# display_zm1000.net
KiCad netlist of a schematic drawn in EAGLE
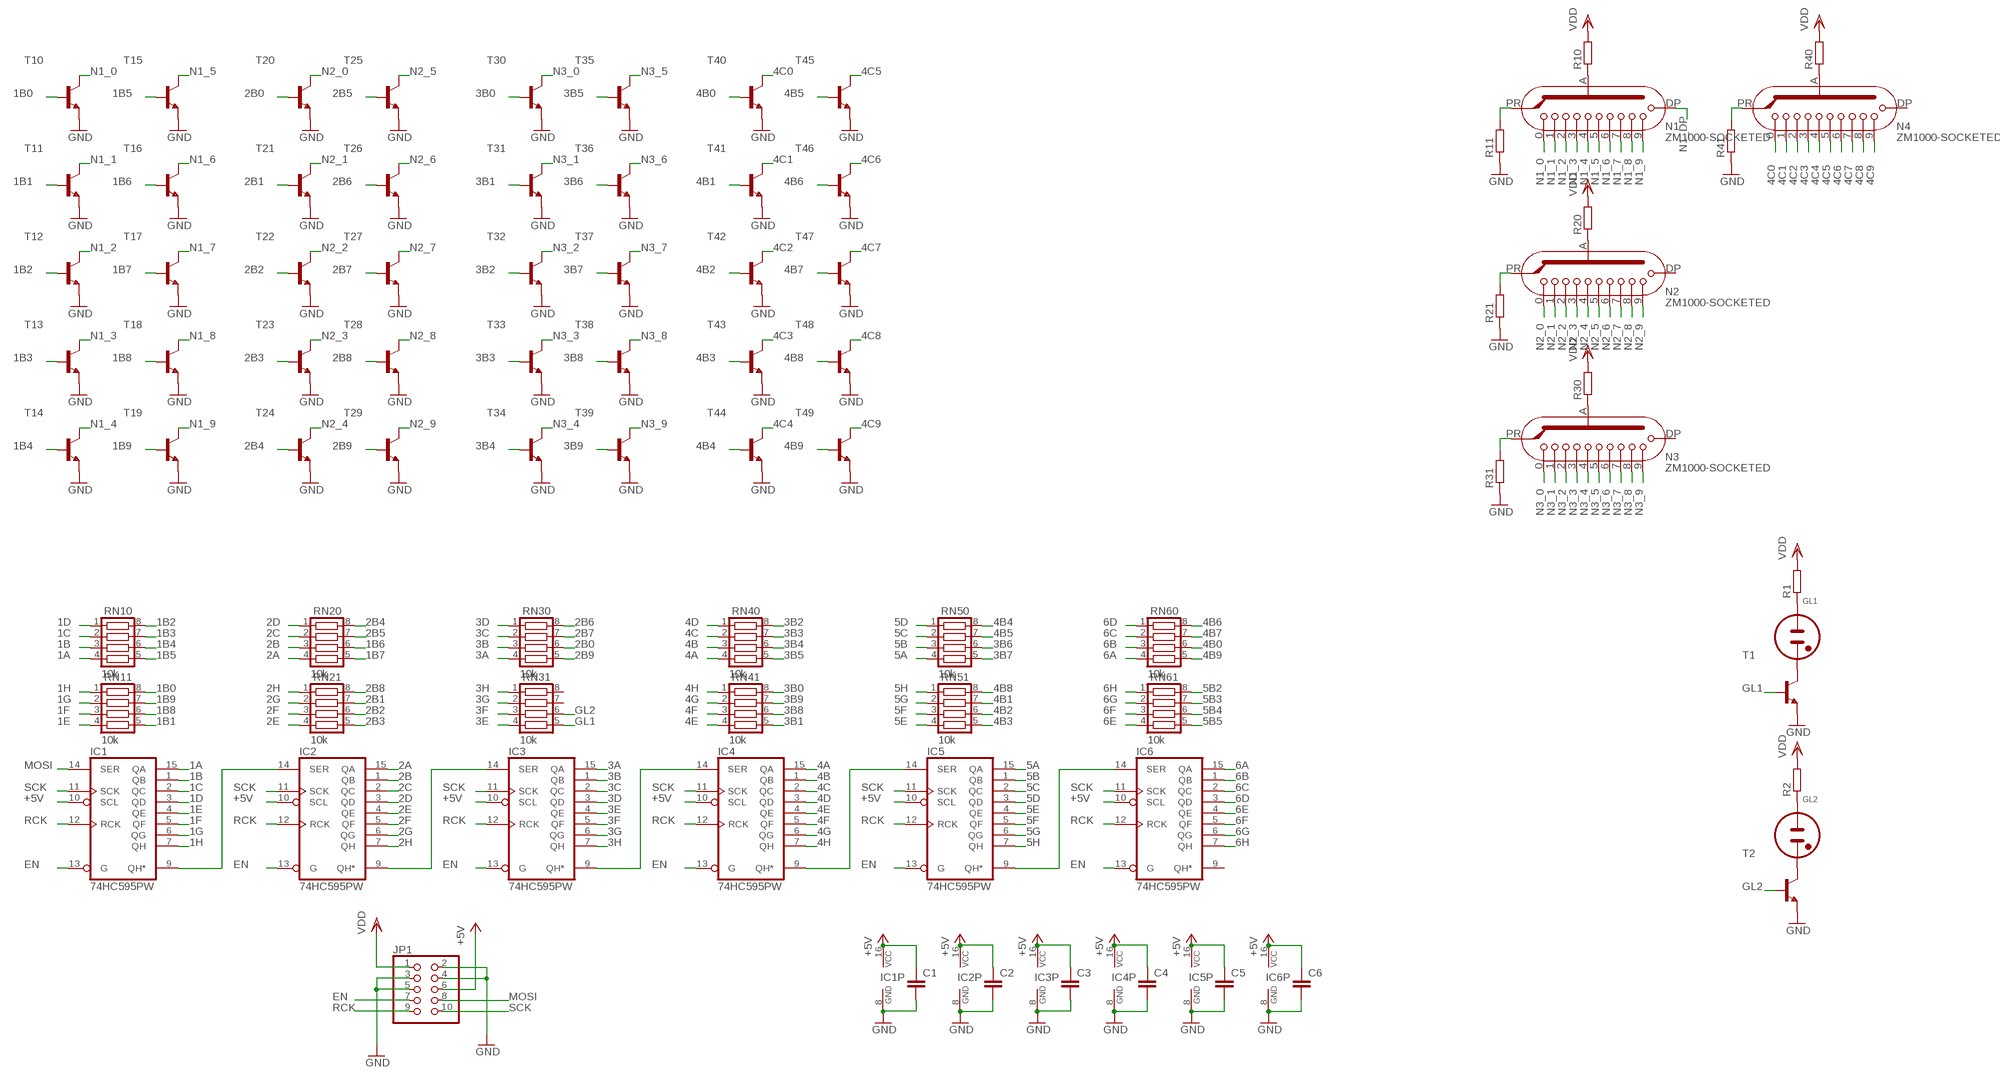
[diagram p0: schematic, sheet 1]

(export (version "E")
  (design (tool "Eeschema 10.0.6"))
  (components
    (comp (ref "C1")
      (value "C-EUC0603")
      (footprint "eagle-import:C0603")
      (libsource (lib "eagle-import") (part "C-EUC0603"))
    )
    (comp (ref "C2")
      (value "C-EUC0603")
      (footprint "eagle-import:C0603")
      (libsource (lib "eagle-import") (part "C-EUC0603"))
    )
    (comp (ref "C3")
      (value "C-EUC0603")
      (footprint "eagle-import:C0603")
      (libsource (lib "eagle-import") (part "C-EUC0603"))
    )
    (comp (ref "C4")
      (value "C-EUC0603")
      (footprint "eagle-import:C0603")
      (libsource (lib "eagle-import") (part "C-EUC0603"))
    )
    (comp (ref "C5")
      (value "C-EUC0603")
      (footprint "eagle-import:C0603")
      (libsource (lib "eagle-import") (part "C-EUC0603"))
    )
    (comp (ref "C6")
      (value "C-EUC0603")
      (footprint "eagle-import:C0603")
      (libsource (lib "eagle-import") (part "C-EUC0603"))
    )
    (comp (ref "GL1")
      (value "NE2-NEON-BULB-DRILL")
      (footprint "eagle-import:NE2-NEON-BULB-DRILL")
      (libsource (lib "eagle-import") (part "NE2-NEON-BULB-DRILL"))
    )
    (comp (ref "GL2")
      (value "NE2-NEON-BULB-DRILL")
      (footprint "eagle-import:NE2-NEON-BULB-DRILL")
      (libsource (lib "eagle-import") (part "NE2-NEON-BULB-DRILL"))
    )
    (comp (ref "IC1")
      (value "74HC595PW")
      (footprint "eagle-import:TSSOP16")
      (libsource (lib "eagle-import") (part "74595PWHC"))
    )
    (comp (ref "IC2")
      (value "74HC595PW")
      (footprint "eagle-import:TSSOP16")
      (libsource (lib "eagle-import") (part "74595PWHC"))
    )
    (comp (ref "IC3")
      (value "74HC595PW")
      (footprint "eagle-import:TSSOP16")
      (libsource (lib "eagle-import") (part "74595PWHC"))
    )
    (comp (ref "IC4")
      (value "74HC595PW")
      (footprint "eagle-import:TSSOP16")
      (libsource (lib "eagle-import") (part "74595PWHC"))
    )
    (comp (ref "IC5")
      (value "74HC595PW")
      (footprint "eagle-import:TSSOP16")
      (libsource (lib "eagle-import") (part "74595PWHC"))
    )
    (comp (ref "IC6")
      (value "74HC595PW")
      (footprint "eagle-import:TSSOP16")
      (libsource (lib "eagle-import") (part "74595PWHC"))
    )
    (comp (ref "JP1")
      (value "PINHD-2X5_2.54-SMD")
      (footprint "eagle-import:2X05SMD")
      (libsource (lib "eagle-import") (part "PINHD-2X5_2.54-SMD"))
    )
    (comp (ref "N1")
      (value "ZM1000-SOCKETED")
      (footprint "eagle-import:ZM1000-SOCKETED")
      (libsource (lib "eagle-import") (part "ZM1000-SOCKETED"))
    )
    (comp (ref "N2")
      (value "ZM1000-SOCKETED")
      (footprint "eagle-import:ZM1000-SOCKETED")
      (libsource (lib "eagle-import") (part "ZM1000-SOCKETED"))
    )
    (comp (ref "N3")
      (value "ZM1000-SOCKETED")
      (footprint "eagle-import:ZM1000-SOCKETED")
      (libsource (lib "eagle-import") (part "ZM1000-SOCKETED"))
    )
    (comp (ref "N4")
      (value "ZM1000-SOCKETED")
      (footprint "eagle-import:ZM1000-SOCKETED")
      (libsource (lib "eagle-import") (part "ZM1000-SOCKETED"))
    )
    (comp (ref "R1")
      (value "R-EU_R0603")
      (footprint "eagle-import:R0603")
      (libsource (lib "eagle-import") (part "R-EU_R0603"))
    )
    (comp (ref "R2")
      (value "R-EU_R0603")
      (footprint "eagle-import:R0603")
      (libsource (lib "eagle-import") (part "R-EU_R0603"))
    )
    (comp (ref "R10")
      (value "R-EU_R0603")
      (footprint "eagle-import:R0603")
      (libsource (lib "eagle-import") (part "R-EU_R0603"))
    )
    (comp (ref "R11")
      (value "R-EU_R0603")
      (footprint "eagle-import:R0603")
      (libsource (lib "eagle-import") (part "R-EU_R0603"))
    )
    (comp (ref "R20")
      (value "R-EU_R0603")
      (footprint "eagle-import:R0603")
      (libsource (lib "eagle-import") (part "R-EU_R0603"))
    )
    (comp (ref "R21")
      (value "R-EU_R0603")
      (footprint "eagle-import:R0603")
      (libsource (lib "eagle-import") (part "R-EU_R0603"))
    )
    (comp (ref "R30")
      (value "R-EU_R0603")
      (footprint "eagle-import:R0603")
      (libsource (lib "eagle-import") (part "R-EU_R0603"))
    )
    (comp (ref "R31")
      (value "R-EU_R0603")
      (footprint "eagle-import:R0603")
      (libsource (lib "eagle-import") (part "R-EU_R0603"))
    )
    (comp (ref "R40")
      (value "R-EU_R0603")
      (footprint "eagle-import:R0603")
      (libsource (lib "eagle-import") (part "R-EU_R0603"))
    )
    (comp (ref "R41")
      (value "R-EU_R0603")
      (footprint "eagle-import:R0603")
      (libsource (lib "eagle-import") (part "R-EU_R0603"))
    )
    (comp (ref "RN10")
      (value "10k")
      (footprint "eagle-import:CTS742C083")
      (fields (field (name "OC_FARNELL") "unknown") (field (name "OC_NEWARK") "unknown"))
      (libsource (lib "eagle-import") (part "CTS742C083"))
    )
    (comp (ref "RN11")
      (value "10k")
      (footprint "eagle-import:CTS742C083")
      (fields (field (name "OC_FARNELL") "unknown") (field (name "OC_NEWARK") "unknown"))
      (libsource (lib "eagle-import") (part "CTS742C083"))
    )
    (comp (ref "RN20")
      (value "10k")
      (footprint "eagle-import:CTS742C083")
      (fields (field (name "OC_FARNELL") "unknown") (field (name "OC_NEWARK") "unknown"))
      (libsource (lib "eagle-import") (part "CTS742C083"))
    )
    (comp (ref "RN21")
      (value "10k")
      (footprint "eagle-import:CTS742C083")
      (fields (field (name "OC_FARNELL") "unknown") (field (name "OC_NEWARK") "unknown"))
      (libsource (lib "eagle-import") (part "CTS742C083"))
    )
    (comp (ref "RN30")
      (value "10k")
      (footprint "eagle-import:CTS742C083")
      (fields (field (name "OC_FARNELL") "unknown") (field (name "OC_NEWARK") "unknown"))
      (libsource (lib "eagle-import") (part "CTS742C083"))
    )
    (comp (ref "RN31")
      (value "10k")
      (footprint "eagle-import:CTS742C083")
      (fields (field (name "OC_FARNELL") "unknown") (field (name "OC_NEWARK") "unknown"))
      (libsource (lib "eagle-import") (part "CTS742C083"))
    )
    (comp (ref "RN40")
      (value "10k")
      (footprint "eagle-import:CTS742C083")
      (fields (field (name "OC_FARNELL") "unknown") (field (name "OC_NEWARK") "unknown"))
      (libsource (lib "eagle-import") (part "CTS742C083"))
    )
    (comp (ref "RN41")
      (value "10k")
      (footprint "eagle-import:CTS742C083")
      (fields (field (name "OC_FARNELL") "unknown") (field (name "OC_NEWARK") "unknown"))
      (libsource (lib "eagle-import") (part "CTS742C083"))
    )
    (comp (ref "RN50")
      (value "10k")
      (footprint "eagle-import:CTS742C083")
      (fields (field (name "OC_FARNELL") "unknown") (field (name "OC_NEWARK") "unknown"))
      (libsource (lib "eagle-import") (part "CTS742C083"))
    )
    (comp (ref "RN51")
      (value "10k")
      (footprint "eagle-import:CTS742C083")
      (fields (field (name "OC_FARNELL") "unknown") (field (name "OC_NEWARK") "unknown"))
      (libsource (lib "eagle-import") (part "CTS742C083"))
    )
    (comp (ref "RN60")
      (value "10k")
      (footprint "eagle-import:CTS742C083")
      (fields (field (name "OC_FARNELL") "unknown") (field (name "OC_NEWARK") "unknown"))
      (libsource (lib "eagle-import") (part "CTS742C083"))
    )
    (comp (ref "RN61")
      (value "10k")
      (footprint "eagle-import:CTS742C083")
      (fields (field (name "OC_FARNELL") "unknown") (field (name "OC_NEWARK") "unknown"))
      (libsource (lib "eagle-import") (part "CTS742C083"))
    )
    (comp (ref "T1")
      (value "SMBTA42")
      (footprint "eagle-import:SOT23")
      (libsource (lib "eagle-import") (part "SMBTA42"))
    )
    (comp (ref "T2")
      (value "SMBTA42")
      (footprint "eagle-import:SOT23")
      (libsource (lib "eagle-import") (part "SMBTA42"))
    )
    (comp (ref "T10")
      (value "SMBTA42")
      (footprint "eagle-import:SOT23")
      (libsource (lib "eagle-import") (part "SMBTA42"))
    )
    (comp (ref "T11")
      (value "SMBTA42")
      (footprint "eagle-import:SOT23")
      (libsource (lib "eagle-import") (part "SMBTA42"))
    )
    (comp (ref "T12")
      (value "SMBTA42")
      (footprint "eagle-import:SOT23")
      (libsource (lib "eagle-import") (part "SMBTA42"))
    )
    (comp (ref "T13")
      (value "SMBTA42")
      (footprint "eagle-import:SOT23")
      (libsource (lib "eagle-import") (part "SMBTA42"))
    )
    (comp (ref "T14")
      (value "SMBTA42")
      (footprint "eagle-import:SOT23")
      (libsource (lib "eagle-import") (part "SMBTA42"))
    )
    (comp (ref "T15")
      (value "SMBTA42")
      (footprint "eagle-import:SOT23")
      (libsource (lib "eagle-import") (part "SMBTA42"))
    )
    (comp (ref "T16")
      (value "SMBTA42")
      (footprint "eagle-import:SOT23")
      (libsource (lib "eagle-import") (part "SMBTA42"))
    )
    (comp (ref "T17")
      (value "SMBTA42")
      (footprint "eagle-import:SOT23")
      (libsource (lib "eagle-import") (part "SMBTA42"))
    )
    (comp (ref "T18")
      (value "SMBTA42")
      (footprint "eagle-import:SOT23")
      (libsource (lib "eagle-import") (part "SMBTA42"))
    )
    (comp (ref "T19")
      (value "SMBTA42")
      (footprint "eagle-import:SOT23")
      (libsource (lib "eagle-import") (part "SMBTA42"))
    )
    (comp (ref "T20")
      (value "SMBTA42")
      (footprint "eagle-import:SOT23")
      (libsource (lib "eagle-import") (part "SMBTA42"))
    )
    (comp (ref "T21")
      (value "SMBTA42")
      (footprint "eagle-import:SOT23")
      (libsource (lib "eagle-import") (part "SMBTA42"))
    )
    (comp (ref "T22")
      (value "SMBTA42")
      (footprint "eagle-import:SOT23")
      (libsource (lib "eagle-import") (part "SMBTA42"))
    )
    (comp (ref "T23")
      (value "SMBTA42")
      (footprint "eagle-import:SOT23")
      (libsource (lib "eagle-import") (part "SMBTA42"))
    )
    (comp (ref "T24")
      (value "SMBTA42")
      (footprint "eagle-import:SOT23")
      (libsource (lib "eagle-import") (part "SMBTA42"))
    )
    (comp (ref "T25")
      (value "SMBTA42")
      (footprint "eagle-import:SOT23")
      (libsource (lib "eagle-import") (part "SMBTA42"))
    )
    (comp (ref "T26")
      (value "SMBTA42")
      (footprint "eagle-import:SOT23")
      (libsource (lib "eagle-import") (part "SMBTA42"))
    )
    (comp (ref "T27")
      (value "SMBTA42")
      (footprint "eagle-import:SOT23")
      (libsource (lib "eagle-import") (part "SMBTA42"))
    )
    (comp (ref "T28")
      (value "SMBTA42")
      (footprint "eagle-import:SOT23")
      (libsource (lib "eagle-import") (part "SMBTA42"))
    )
    (comp (ref "T29")
      (value "SMBTA42")
      (footprint "eagle-import:SOT23")
      (libsource (lib "eagle-import") (part "SMBTA42"))
    )
    (comp (ref "T30")
      (value "SMBTA42")
      (footprint "eagle-import:SOT23")
      (libsource (lib "eagle-import") (part "SMBTA42"))
    )
    (comp (ref "T31")
      (value "SMBTA42")
      (footprint "eagle-import:SOT23")
      (libsource (lib "eagle-import") (part "SMBTA42"))
    )
    (comp (ref "T32")
      (value "SMBTA42")
      (footprint "eagle-import:SOT23")
      (libsource (lib "eagle-import") (part "SMBTA42"))
    )
    (comp (ref "T33")
      (value "SMBTA42")
      (footprint "eagle-import:SOT23")
      (libsource (lib "eagle-import") (part "SMBTA42"))
    )
    (comp (ref "T34")
      (value "SMBTA42")
      (footprint "eagle-import:SOT23")
      (libsource (lib "eagle-import") (part "SMBTA42"))
    )
    (comp (ref "T35")
      (value "SMBTA42")
      (footprint "eagle-import:SOT23")
      (libsource (lib "eagle-import") (part "SMBTA42"))
    )
    (comp (ref "T36")
      (value "SMBTA42")
      (footprint "eagle-import:SOT23")
      (libsource (lib "eagle-import") (part "SMBTA42"))
    )
    (comp (ref "T37")
      (value "SMBTA42")
      (footprint "eagle-import:SOT23")
      (libsource (lib "eagle-import") (part "SMBTA42"))
    )
    (comp (ref "T38")
      (value "SMBTA42")
      (footprint "eagle-import:SOT23")
      (libsource (lib "eagle-import") (part "SMBTA42"))
    )
    (comp (ref "T39")
      (value "SMBTA42")
      (footprint "eagle-import:SOT23")
      (libsource (lib "eagle-import") (part "SMBTA42"))
    )
    (comp (ref "T40")
      (value "SMBTA42")
      (footprint "eagle-import:SOT23")
      (libsource (lib "eagle-import") (part "SMBTA42"))
    )
    (comp (ref "T41")
      (value "SMBTA42")
      (footprint "eagle-import:SOT23")
      (libsource (lib "eagle-import") (part "SMBTA42"))
    )
    (comp (ref "T42")
      (value "SMBTA42")
      (footprint "eagle-import:SOT23")
      (libsource (lib "eagle-import") (part "SMBTA42"))
    )
    (comp (ref "T43")
      (value "SMBTA42")
      (footprint "eagle-import:SOT23")
      (libsource (lib "eagle-import") (part "SMBTA42"))
    )
    (comp (ref "T44")
      (value "SMBTA42")
      (footprint "eagle-import:SOT23")
      (libsource (lib "eagle-import") (part "SMBTA42"))
    )
    (comp (ref "T45")
      (value "SMBTA42")
      (footprint "eagle-import:SOT23")
      (libsource (lib "eagle-import") (part "SMBTA42"))
    )
    (comp (ref "T46")
      (value "SMBTA42")
      (footprint "eagle-import:SOT23")
      (libsource (lib "eagle-import") (part "SMBTA42"))
    )
    (comp (ref "T47")
      (value "SMBTA42")
      (footprint "eagle-import:SOT23")
      (libsource (lib "eagle-import") (part "SMBTA42"))
    )
    (comp (ref "T48")
      (value "SMBTA42")
      (footprint "eagle-import:SOT23")
      (libsource (lib "eagle-import") (part "SMBTA42"))
    )
    (comp (ref "T49")
      (value "SMBTA42")
      (footprint "eagle-import:SOT23")
      (libsource (lib "eagle-import") (part "SMBTA42"))
    )
  )
  (nets
    (net (code "1") (name "+5V") (class "Default")
      (node (ref "C1") (pin "1") (pinfunction "1_1") (pintype "passive"))
      (node (ref "C2") (pin "1") (pinfunction "1_1") (pintype "passive"))
      (node (ref "C3") (pin "1") (pinfunction "1_1") (pintype "passive"))
      (node (ref "C4") (pin "1") (pinfunction "1_1") (pintype "passive"))
      (node (ref "C5") (pin "1") (pinfunction "1_1") (pintype "passive"))
      (node (ref "C6") (pin "1") (pinfunction "1_1") (pintype "passive"))
      (node (ref "IC1") (pin "10") (pinfunction "SCL_10") (pintype "input"))
      (node (ref "IC1") (pin "16") (pinfunction "VCC_16") (pintype "power_in"))
      (node (ref "IC2") (pin "10") (pinfunction "SCL_10") (pintype "input"))
      (node (ref "IC2") (pin "16") (pinfunction "VCC_16") (pintype "power_in"))
      (node (ref "IC3") (pin "10") (pinfunction "SCL_10") (pintype "input"))
      (node (ref "IC3") (pin "16") (pinfunction "VCC_16") (pintype "power_in"))
      (node (ref "IC4") (pin "10") (pinfunction "SCL_10") (pintype "input"))
      (node (ref "IC4") (pin "16") (pinfunction "VCC_16") (pintype "power_in"))
      (node (ref "IC5") (pin "10") (pinfunction "SCL_10") (pintype "input"))
      (node (ref "IC5") (pin "16") (pinfunction "VCC_16") (pintype "power_in"))
      (node (ref "IC6") (pin "10") (pinfunction "SCL_10") (pintype "input"))
      (node (ref "IC6") (pin "16") (pinfunction "VCC_16") (pintype "power_in"))
      (node (ref "JP1") (pin "6") (pinfunction "6_6") (pintype "passive"))
    )
    (net (code "2") (name "/1A") (class "Default")
      (node (ref "IC1") (pin "15") (pinfunction "QA_15") (pintype "tri_state"))
      (node (ref "RN10") (pin "4") (pinfunction "4_4") (pintype "passive"))
    )
    (net (code "3") (name "/1B") (class "Default")
      (node (ref "IC1") (pin "1") (pinfunction "QB_1") (pintype "tri_state"))
      (node (ref "RN10") (pin "3") (pinfunction "3_3") (pintype "passive"))
    )
    (net (code "4") (name "/1B0") (class "Default")
      (node (ref "RN11") (pin "8") (pinfunction "8_8") (pintype "passive"))
      (node (ref "T10") (pin "1") (pinfunction "B_1") (pintype "passive"))
    )
    (net (code "5") (name "/1B1") (class "Default")
      (node (ref "RN11") (pin "5") (pinfunction "5_5") (pintype "passive"))
      (node (ref "T11") (pin "1") (pinfunction "B_1") (pintype "passive"))
    )
    (net (code "6") (name "/1B2") (class "Default")
      (node (ref "RN10") (pin "8") (pinfunction "8_8") (pintype "passive"))
      (node (ref "T12") (pin "1") (pinfunction "B_1") (pintype "passive"))
    )
    (net (code "7") (name "/1B3") (class "Default")
      (node (ref "RN10") (pin "7") (pinfunction "7_7") (pintype "passive"))
      (node (ref "T13") (pin "1") (pinfunction "B_1") (pintype "passive"))
    )
    (net (code "8") (name "/1B4") (class "Default")
      (node (ref "RN10") (pin "6") (pinfunction "6_6") (pintype "passive"))
      (node (ref "T14") (pin "1") (pinfunction "B_1") (pintype "passive"))
    )
    (net (code "9") (name "/1B5") (class "Default")
      (node (ref "RN10") (pin "5") (pinfunction "5_5") (pintype "passive"))
      (node (ref "T15") (pin "1") (pinfunction "B_1") (pintype "passive"))
    )
    (net (code "10") (name "/1B6") (class "Default")
      (node (ref "RN20") (pin "6") (pinfunction "6_6") (pintype "passive"))
      (node (ref "T16") (pin "1") (pinfunction "B_1") (pintype "passive"))
    )
    (net (code "11") (name "/1B7") (class "Default")
      (node (ref "RN20") (pin "5") (pinfunction "5_5") (pintype "passive"))
      (node (ref "T17") (pin "1") (pinfunction "B_1") (pintype "passive"))
    )
    (net (code "12") (name "/1B8") (class "Default")
      (node (ref "RN11") (pin "6") (pinfunction "6_6") (pintype "passive"))
      (node (ref "T18") (pin "1") (pinfunction "B_1") (pintype "passive"))
    )
    (net (code "13") (name "/1B9") (class "Default")
      (node (ref "RN11") (pin "7") (pinfunction "7_7") (pintype "passive"))
      (node (ref "T19") (pin "1") (pinfunction "B_1") (pintype "passive"))
    )
    (net (code "14") (name "/1C") (class "Default")
      (node (ref "IC1") (pin "2") (pinfunction "QC_2") (pintype "tri_state"))
      (node (ref "RN10") (pin "2") (pinfunction "2_2") (pintype "passive"))
    )
    (net (code "15") (name "/1D") (class "Default")
      (node (ref "IC1") (pin "3") (pinfunction "QD_3") (pintype "tri_state"))
      (node (ref "RN10") (pin "1") (pinfunction "1_1") (pintype "passive"))
    )
    (net (code "16") (name "/1E") (class "Default")
      (node (ref "IC1") (pin "4") (pinfunction "QE_4") (pintype "tri_state"))
      (node (ref "RN11") (pin "4") (pinfunction "4_4") (pintype "passive"))
    )
    (net (code "17") (name "/1F") (class "Default")
      (node (ref "IC1") (pin "5") (pinfunction "QF_5") (pintype "tri_state"))
      (node (ref "RN11") (pin "3") (pinfunction "3_3") (pintype "passive"))
    )
    (net (code "18") (name "/1G") (class "Default")
      (node (ref "IC1") (pin "6") (pinfunction "QG_6") (pintype "tri_state"))
      (node (ref "RN11") (pin "2") (pinfunction "2_2") (pintype "passive"))
    )
    (net (code "19") (name "/1H") (class "Default")
      (node (ref "IC1") (pin "7") (pinfunction "QH_7") (pintype "tri_state"))
      (node (ref "RN11") (pin "1") (pinfunction "1_1") (pintype "passive"))
    )
    (net (code "20") (name "/2A") (class "Default")
      (node (ref "IC2") (pin "15") (pinfunction "QA_15") (pintype "tri_state"))
      (node (ref "RN20") (pin "4") (pinfunction "4_4") (pintype "passive"))
    )
    (net (code "21") (name "/2B") (class "Default")
      (node (ref "IC2") (pin "1") (pinfunction "QB_1") (pintype "tri_state"))
      (node (ref "RN20") (pin "3") (pinfunction "3_3") (pintype "passive"))
    )
    (net (code "22") (name "/2B0") (class "Default")
      (node (ref "RN30") (pin "6") (pinfunction "6_6") (pintype "passive"))
      (node (ref "T20") (pin "1") (pinfunction "B_1") (pintype "passive"))
    )
    (net (code "23") (name "/2B1") (class "Default")
      (node (ref "RN21") (pin "7") (pinfunction "7_7") (pintype "passive"))
      (node (ref "T21") (pin "1") (pinfunction "B_1") (pintype "passive"))
    )
    (net (code "24") (name "/2B2") (class "Default")
      (node (ref "RN21") (pin "6") (pinfunction "6_6") (pintype "passive"))
      (node (ref "T22") (pin "1") (pinfunction "B_1") (pintype "passive"))
    )
    (net (code "25") (name "/2B3") (class "Default")
      (node (ref "RN21") (pin "5") (pinfunction "5_5") (pintype "passive"))
      (node (ref "T23") (pin "1") (pinfunction "B_1") (pintype "passive"))
    )
    (net (code "26") (name "/2B4") (class "Default")
      (node (ref "RN20") (pin "8") (pinfunction "8_8") (pintype "passive"))
      (node (ref "T24") (pin "1") (pinfunction "B_1") (pintype "passive"))
    )
    (net (code "27") (name "/2B5") (class "Default")
      (node (ref "RN20") (pin "7") (pinfunction "7_7") (pintype "passive"))
      (node (ref "T25") (pin "1") (pinfunction "B_1") (pintype "passive"))
    )
    (net (code "28") (name "/2B6") (class "Default")
      (node (ref "RN30") (pin "8") (pinfunction "8_8") (pintype "passive"))
      (node (ref "T26") (pin "1") (pinfunction "B_1") (pintype "passive"))
    )
    (net (code "29") (name "/2B7") (class "Default")
      (node (ref "RN30") (pin "7") (pinfunction "7_7") (pintype "passive"))
      (node (ref "T27") (pin "1") (pinfunction "B_1") (pintype "passive"))
    )
    (net (code "30") (name "/2B8") (class "Default")
      (node (ref "RN21") (pin "8") (pinfunction "8_8") (pintype "passive"))
      (node (ref "T28") (pin "1") (pinfunction "B_1") (pintype "passive"))
    )
    (net (code "31") (name "/2B9") (class "Default")
      (node (ref "RN30") (pin "5") (pinfunction "5_5") (pintype "passive"))
      (node (ref "T29") (pin "1") (pinfunction "B_1") (pintype "passive"))
    )
    (net (code "32") (name "/2C") (class "Default")
      (node (ref "IC2") (pin "2") (pinfunction "QC_2") (pintype "tri_state"))
      (node (ref "RN20") (pin "2") (pinfunction "2_2") (pintype "passive"))
    )
    (net (code "33") (name "/2D") (class "Default")
      (node (ref "IC2") (pin "3") (pinfunction "QD_3") (pintype "tri_state"))
      (node (ref "RN20") (pin "1") (pinfunction "1_1") (pintype "passive"))
    )
    (net (code "34") (name "/2E") (class "Default")
      (node (ref "IC2") (pin "4") (pinfunction "QE_4") (pintype "tri_state"))
      (node (ref "RN21") (pin "4") (pinfunction "4_4") (pintype "passive"))
    )
    (net (code "35") (name "/2F") (class "Default")
      (node (ref "IC2") (pin "5") (pinfunction "QF_5") (pintype "tri_state"))
      (node (ref "RN21") (pin "3") (pinfunction "3_3") (pintype "passive"))
    )
    (net (code "36") (name "/2G") (class "Default")
      (node (ref "IC2") (pin "6") (pinfunction "QG_6") (pintype "tri_state"))
      (node (ref "RN21") (pin "2") (pinfunction "2_2") (pintype "passive"))
    )
    (net (code "37") (name "/2H") (class "Default")
      (node (ref "IC2") (pin "7") (pinfunction "QH_7") (pintype "tri_state"))
      (node (ref "RN21") (pin "1") (pinfunction "1_1") (pintype "passive"))
    )
    (net (code "38") (name "/3A") (class "Default")
      (node (ref "IC3") (pin "15") (pinfunction "QA_15") (pintype "tri_state"))
      (node (ref "RN30") (pin "4") (pinfunction "4_4") (pintype "passive"))
    )
    (net (code "39") (name "/3B") (class "Default")
      (node (ref "IC3") (pin "1") (pinfunction "QB_1") (pintype "tri_state"))
      (node (ref "RN30") (pin "3") (pinfunction "3_3") (pintype "passive"))
    )
    (net (code "40") (name "/3B0") (class "Default")
      (node (ref "RN41") (pin "8") (pinfunction "8_8") (pintype "passive"))
      (node (ref "T30") (pin "1") (pinfunction "B_1") (pintype "passive"))
    )
    (net (code "41") (name "/3B1") (class "Default")
      (node (ref "RN41") (pin "5") (pinfunction "5_5") (pintype "passive"))
      (node (ref "T31") (pin "1") (pinfunction "B_1") (pintype "passive"))
    )
    (net (code "42") (name "/3B2") (class "Default")
      (node (ref "RN40") (pin "8") (pinfunction "8_8") (pintype "passive"))
      (node (ref "T32") (pin "1") (pinfunction "B_1") (pintype "passive"))
    )
    (net (code "43") (name "/3B3") (class "Default")
      (node (ref "RN40") (pin "7") (pinfunction "7_7") (pintype "passive"))
      (node (ref "T33") (pin "1") (pinfunction "B_1") (pintype "passive"))
    )
    (net (code "44") (name "/3B4") (class "Default")
      (node (ref "RN40") (pin "6") (pinfunction "6_6") (pintype "passive"))
      (node (ref "T34") (pin "1") (pinfunction "B_1") (pintype "passive"))
    )
    (net (code "45") (name "/3B5") (class "Default")
      (node (ref "RN40") (pin "5") (pinfunction "5_5") (pintype "passive"))
      (node (ref "T35") (pin "1") (pinfunction "B_1") (pintype "passive"))
    )
    (net (code "46") (name "/3B6") (class "Default")
      (node (ref "RN50") (pin "6") (pinfunction "6_6") (pintype "passive"))
      (node (ref "T36") (pin "1") (pinfunction "B_1") (pintype "passive"))
    )
    (net (code "47") (name "/3B7") (class "Default")
      (node (ref "RN50") (pin "5") (pinfunction "5_5") (pintype "passive"))
      (node (ref "T37") (pin "1") (pinfunction "B_1") (pintype "passive"))
    )
    (net (code "48") (name "/3B8") (class "Default")
      (node (ref "RN41") (pin "6") (pinfunction "6_6") (pintype "passive"))
      (node (ref "T38") (pin "1") (pinfunction "B_1") (pintype "passive"))
    )
    (net (code "49") (name "/3B9") (class "Default")
      (node (ref "RN41") (pin "7") (pinfunction "7_7") (pintype "passive"))
      (node (ref "T39") (pin "1") (pinfunction "B_1") (pintype "passive"))
    )
    (net (code "50") (name "/3C") (class "Default")
      (node (ref "IC3") (pin "2") (pinfunction "QC_2") (pintype "tri_state"))
      (node (ref "RN30") (pin "2") (pinfunction "2_2") (pintype "passive"))
    )
    (net (code "51") (name "/3D") (class "Default")
      (node (ref "IC3") (pin "3") (pinfunction "QD_3") (pintype "tri_state"))
      (node (ref "RN30") (pin "1") (pinfunction "1_1") (pintype "passive"))
    )
    (net (code "52") (name "/3E") (class "Default")
      (node (ref "IC3") (pin "4") (pinfunction "QE_4") (pintype "tri_state"))
      (node (ref "RN31") (pin "4") (pinfunction "4_4") (pintype "passive"))
    )
    (net (code "53") (name "/3F") (class "Default")
      (node (ref "IC3") (pin "5") (pinfunction "QF_5") (pintype "tri_state"))
      (node (ref "RN31") (pin "3") (pinfunction "3_3") (pintype "passive"))
    )
    (net (code "54") (name "/3G") (class "Default")
      (node (ref "IC3") (pin "6") (pinfunction "QG_6") (pintype "tri_state"))
      (node (ref "RN31") (pin "2") (pinfunction "2_2") (pintype "passive"))
    )
    (net (code "55") (name "/3H") (class "Default")
      (node (ref "IC3") (pin "7") (pinfunction "QH_7") (pintype "tri_state"))
      (node (ref "RN31") (pin "1") (pinfunction "1_1") (pintype "passive"))
    )
    (net (code "56") (name "/4A") (class "Default")
      (node (ref "IC4") (pin "15") (pinfunction "QA_15") (pintype "tri_state"))
      (node (ref "RN40") (pin "4") (pinfunction "4_4") (pintype "passive"))
    )
    (net (code "57") (name "/4B") (class "Default")
      (node (ref "IC4") (pin "1") (pinfunction "QB_1") (pintype "tri_state"))
      (node (ref "RN40") (pin "3") (pinfunction "3_3") (pintype "passive"))
    )
    (net (code "58") (name "/4B0") (class "Default")
      (node (ref "RN60") (pin "6") (pinfunction "6_6") (pintype "passive"))
      (node (ref "T40") (pin "1") (pinfunction "B_1") (pintype "passive"))
    )
    (net (code "59") (name "/4B1") (class "Default")
      (node (ref "RN51") (pin "7") (pinfunction "7_7") (pintype "passive"))
      (node (ref "T41") (pin "1") (pinfunction "B_1") (pintype "passive"))
    )
    (net (code "60") (name "/4B2") (class "Default")
      (node (ref "RN51") (pin "6") (pinfunction "6_6") (pintype "passive"))
      (node (ref "T42") (pin "1") (pinfunction "B_1") (pintype "passive"))
    )
    (net (code "61") (name "/4B3") (class "Default")
      (node (ref "RN51") (pin "5") (pinfunction "5_5") (pintype "passive"))
      (node (ref "T43") (pin "1") (pinfunction "B_1") (pintype "passive"))
    )
    (net (code "62") (name "/4B4") (class "Default")
      (node (ref "RN50") (pin "8") (pinfunction "8_8") (pintype "passive"))
      (node (ref "T44") (pin "1") (pinfunction "B_1") (pintype "passive"))
    )
    (net (code "63") (name "/4B5") (class "Default")
      (node (ref "RN50") (pin "7") (pinfunction "7_7") (pintype "passive"))
      (node (ref "T45") (pin "1") (pinfunction "B_1") (pintype "passive"))
    )
    (net (code "64") (name "/4B6") (class "Default")
      (node (ref "RN60") (pin "8") (pinfunction "8_8") (pintype "passive"))
      (node (ref "T46") (pin "1") (pinfunction "B_1") (pintype "passive"))
    )
    (net (code "65") (name "/4B7") (class "Default")
      (node (ref "RN60") (pin "7") (pinfunction "7_7") (pintype "passive"))
      (node (ref "T47") (pin "1") (pinfunction "B_1") (pintype "passive"))
    )
    (net (code "66") (name "/4B8") (class "Default")
      (node (ref "RN51") (pin "8") (pinfunction "8_8") (pintype "passive"))
      (node (ref "T48") (pin "1") (pinfunction "B_1") (pintype "passive"))
    )
    (net (code "67") (name "/4B9") (class "Default")
      (node (ref "RN60") (pin "5") (pinfunction "5_5") (pintype "passive"))
      (node (ref "T49") (pin "1") (pinfunction "B_1") (pintype "passive"))
    )
    (net (code "68") (name "/4C") (class "Default")
      (node (ref "IC4") (pin "2") (pinfunction "QC_2") (pintype "tri_state"))
      (node (ref "RN40") (pin "2") (pinfunction "2_2") (pintype "passive"))
    )
    (net (code "69") (name "/4C0") (class "Default")
      (node (ref "N4") (pin "K0") (pinfunction "0_K0") (pintype "bidirectional"))
      (node (ref "T40") (pin "3") (pinfunction "C_3") (pintype "passive"))
    )
    (net (code "70") (name "/4C1") (class "Default")
      (node (ref "N4") (pin "K1") (pinfunction "1_K1") (pintype "bidirectional"))
      (node (ref "T41") (pin "3") (pinfunction "C_3") (pintype "passive"))
    )
    (net (code "71") (name "/4C2") (class "Default")
      (node (ref "N4") (pin "K2") (pinfunction "2_K2") (pintype "bidirectional"))
      (node (ref "T42") (pin "3") (pinfunction "C_3") (pintype "passive"))
    )
    (net (code "72") (name "/4C3") (class "Default")
      (node (ref "N4") (pin "K3") (pinfunction "3_K3") (pintype "bidirectional"))
      (node (ref "T43") (pin "3") (pinfunction "C_3") (pintype "passive"))
    )
    (net (code "73") (name "/4C4") (class "Default")
      (node (ref "N4") (pin "K4") (pinfunction "4_K4") (pintype "bidirectional"))
      (node (ref "T44") (pin "3") (pinfunction "C_3") (pintype "passive"))
    )
    (net (code "74") (name "/4C5") (class "Default")
      (node (ref "N4") (pin "K5") (pinfunction "5_K5") (pintype "bidirectional"))
      (node (ref "T45") (pin "3") (pinfunction "C_3") (pintype "passive"))
    )
    (net (code "75") (name "/4C6") (class "Default")
      (node (ref "N4") (pin "K6") (pinfunction "6_K6") (pintype "bidirectional"))
      (node (ref "T46") (pin "3") (pinfunction "C_3") (pintype "passive"))
    )
    (net (code "76") (name "/4C7") (class "Default")
      (node (ref "N4") (pin "K7") (pinfunction "7_K7") (pintype "bidirectional"))
      (node (ref "T47") (pin "3") (pinfunction "C_3") (pintype "passive"))
    )
    (net (code "77") (name "/4C8") (class "Default")
      (node (ref "N4") (pin "K8") (pinfunction "8_K8") (pintype "bidirectional"))
      (node (ref "T48") (pin "3") (pinfunction "C_3") (pintype "passive"))
    )
    (net (code "78") (name "/4C9") (class "Default")
      (node (ref "N4") (pin "K9") (pinfunction "9_K9") (pintype "bidirectional"))
      (node (ref "T49") (pin "3") (pinfunction "C_3") (pintype "passive"))
    )
    (net (code "79") (name "/4D") (class "Default")
      (node (ref "IC4") (pin "3") (pinfunction "QD_3") (pintype "tri_state"))
      (node (ref "RN40") (pin "1") (pinfunction "1_1") (pintype "passive"))
    )
    (net (code "80") (name "/4E") (class "Default")
      (node (ref "IC4") (pin "4") (pinfunction "QE_4") (pintype "tri_state"))
      (node (ref "RN41") (pin "4") (pinfunction "4_4") (pintype "passive"))
    )
    (net (code "81") (name "/4F") (class "Default")
      (node (ref "IC4") (pin "5") (pinfunction "QF_5") (pintype "tri_state"))
      (node (ref "RN41") (pin "3") (pinfunction "3_3") (pintype "passive"))
    )
    (net (code "82") (name "/4G") (class "Default")
      (node (ref "IC4") (pin "6") (pinfunction "QG_6") (pintype "tri_state"))
      (node (ref "RN41") (pin "2") (pinfunction "2_2") (pintype "passive"))
    )
    (net (code "83") (name "/4H") (class "Default")
      (node (ref "IC4") (pin "7") (pinfunction "QH_7") (pintype "tri_state"))
      (node (ref "RN41") (pin "1") (pinfunction "1_1") (pintype "passive"))
    )
    (net (code "84") (name "/5A") (class "Default")
      (node (ref "IC5") (pin "15") (pinfunction "QA_15") (pintype "tri_state"))
      (node (ref "RN50") (pin "4") (pinfunction "4_4") (pintype "passive"))
    )
    (net (code "85") (name "/5B") (class "Default")
      (node (ref "IC5") (pin "1") (pinfunction "QB_1") (pintype "tri_state"))
      (node (ref "RN50") (pin "3") (pinfunction "3_3") (pintype "passive"))
    )
    (net (code "86") (name "/5B2") (class "Default")
      (node (ref "RN61") (pin "8") (pinfunction "8_8") (pintype "passive"))
    )
    (net (code "87") (name "/5B3") (class "Default")
      (node (ref "RN61") (pin "7") (pinfunction "7_7") (pintype "passive"))
    )
    (net (code "88") (name "/5B4") (class "Default")
      (node (ref "RN61") (pin "6") (pinfunction "6_6") (pintype "passive"))
    )
    (net (code "89") (name "/5B5") (class "Default")
      (node (ref "RN61") (pin "5") (pinfunction "5_5") (pintype "passive"))
    )
    (net (code "90") (name "/5C") (class "Default")
      (node (ref "IC5") (pin "2") (pinfunction "QC_2") (pintype "tri_state"))
      (node (ref "RN50") (pin "2") (pinfunction "2_2") (pintype "passive"))
    )
    (net (code "91") (name "/5D") (class "Default")
      (node (ref "IC5") (pin "3") (pinfunction "QD_3") (pintype "tri_state"))
      (node (ref "RN50") (pin "1") (pinfunction "1_1") (pintype "passive"))
    )
    (net (code "92") (name "/5E") (class "Default")
      (node (ref "IC5") (pin "4") (pinfunction "QE_4") (pintype "tri_state"))
      (node (ref "RN51") (pin "4") (pinfunction "4_4") (pintype "passive"))
    )
    (net (code "93") (name "/5F") (class "Default")
      (node (ref "IC5") (pin "5") (pinfunction "QF_5") (pintype "tri_state"))
      (node (ref "RN51") (pin "3") (pinfunction "3_3") (pintype "passive"))
    )
    (net (code "94") (name "/5G") (class "Default")
      (node (ref "IC5") (pin "6") (pinfunction "QG_6") (pintype "tri_state"))
      (node (ref "RN51") (pin "2") (pinfunction "2_2") (pintype "passive"))
    )
    (net (code "95") (name "/5H") (class "Default")
      (node (ref "IC5") (pin "7") (pinfunction "QH_7") (pintype "tri_state"))
      (node (ref "RN51") (pin "1") (pinfunction "1_1") (pintype "passive"))
    )
    (net (code "96") (name "/6A") (class "Default")
      (node (ref "IC6") (pin "15") (pinfunction "QA_15") (pintype "tri_state"))
      (node (ref "RN60") (pin "4") (pinfunction "4_4") (pintype "passive"))
    )
    (net (code "97") (name "/6B") (class "Default")
      (node (ref "IC6") (pin "1") (pinfunction "QB_1") (pintype "tri_state"))
      (node (ref "RN60") (pin "3") (pinfunction "3_3") (pintype "passive"))
    )
    (net (code "98") (name "/6C") (class "Default")
      (node (ref "IC6") (pin "2") (pinfunction "QC_2") (pintype "tri_state"))
      (node (ref "RN60") (pin "2") (pinfunction "2_2") (pintype "passive"))
    )
    (net (code "99") (name "/6D") (class "Default")
      (node (ref "IC6") (pin "3") (pinfunction "QD_3") (pintype "tri_state"))
      (node (ref "RN60") (pin "1") (pinfunction "1_1") (pintype "passive"))
    )
    (net (code "100") (name "/6E") (class "Default")
      (node (ref "IC6") (pin "4") (pinfunction "QE_4") (pintype "tri_state"))
      (node (ref "RN61") (pin "4") (pinfunction "4_4") (pintype "passive"))
    )
    (net (code "101") (name "/6F") (class "Default")
      (node (ref "IC6") (pin "5") (pinfunction "QF_5") (pintype "tri_state"))
      (node (ref "RN61") (pin "3") (pinfunction "3_3") (pintype "passive"))
    )
    (net (code "102") (name "/6G") (class "Default")
      (node (ref "IC6") (pin "6") (pinfunction "QG_6") (pintype "tri_state"))
      (node (ref "RN61") (pin "2") (pinfunction "2_2") (pintype "passive"))
    )
    (net (code "103") (name "/6H") (class "Default")
      (node (ref "IC6") (pin "7") (pinfunction "QH_7") (pintype "tri_state"))
      (node (ref "RN61") (pin "1") (pinfunction "1_1") (pintype "passive"))
    )
    (net (code "104") (name "/EN") (class "Default")
      (node (ref "IC1") (pin "13") (pinfunction "G_13") (pintype "input"))
      (node (ref "IC2") (pin "13") (pinfunction "G_13") (pintype "input"))
      (node (ref "IC3") (pin "13") (pinfunction "G_13") (pintype "input"))
      (node (ref "IC4") (pin "13") (pinfunction "G_13") (pintype "input"))
      (node (ref "IC5") (pin "13") (pinfunction "G_13") (pintype "input"))
      (node (ref "IC6") (pin "13") (pinfunction "G_13") (pintype "input"))
      (node (ref "JP1") (pin "7") (pinfunction "7_7") (pintype "passive"))
    )
    (net (code "105") (name "/GL1") (class "Default")
      (node (ref "RN31") (pin "5") (pinfunction "5_5") (pintype "passive"))
      (node (ref "T1") (pin "1") (pinfunction "B_1") (pintype "passive"))
    )
    (net (code "106") (name "/GL2") (class "Default")
      (node (ref "RN31") (pin "6") (pinfunction "6_6") (pintype "passive"))
      (node (ref "T2") (pin "1") (pinfunction "B_1") (pintype "passive"))
    )
    (net (code "107") (name "/MOSI") (class "Default")
      (node (ref "IC1") (pin "14") (pinfunction "SER_14") (pintype "input"))
      (node (ref "JP1") (pin "8") (pinfunction "8_8") (pintype "passive"))
    )
    (net (code "108") (name "/N1_0") (class "Default")
      (node (ref "N1") (pin "K0") (pinfunction "0_K0") (pintype "bidirectional"))
      (node (ref "T10") (pin "3") (pinfunction "C_3") (pintype "passive"))
    )
    (net (code "109") (name "/N1_1") (class "Default")
      (node (ref "N1") (pin "K1") (pinfunction "1_K1") (pintype "bidirectional"))
      (node (ref "T11") (pin "3") (pinfunction "C_3") (pintype "passive"))
    )
    (net (code "110") (name "/N1_2") (class "Default")
      (node (ref "N1") (pin "K2") (pinfunction "2_K2") (pintype "bidirectional"))
      (node (ref "T12") (pin "3") (pinfunction "C_3") (pintype "passive"))
    )
    (net (code "111") (name "/N1_3") (class "Default")
      (node (ref "N1") (pin "K3") (pinfunction "3_K3") (pintype "bidirectional"))
      (node (ref "T13") (pin "3") (pinfunction "C_3") (pintype "passive"))
    )
    (net (code "112") (name "/N1_4") (class "Default")
      (node (ref "N1") (pin "K4") (pinfunction "4_K4") (pintype "bidirectional"))
      (node (ref "T14") (pin "3") (pinfunction "C_3") (pintype "passive"))
    )
    (net (code "113") (name "/N1_5") (class "Default")
      (node (ref "N1") (pin "K5") (pinfunction "5_K5") (pintype "bidirectional"))
      (node (ref "T15") (pin "3") (pinfunction "C_3") (pintype "passive"))
    )
    (net (code "114") (name "/N1_6") (class "Default")
      (node (ref "N1") (pin "K6") (pinfunction "6_K6") (pintype "bidirectional"))
      (node (ref "T16") (pin "3") (pinfunction "C_3") (pintype "passive"))
    )
    (net (code "115") (name "/N1_7") (class "Default")
      (node (ref "N1") (pin "K7") (pinfunction "7_K7") (pintype "bidirectional"))
      (node (ref "T17") (pin "3") (pinfunction "C_3") (pintype "passive"))
    )
    (net (code "116") (name "/N1_8") (class "Default")
      (node (ref "N1") (pin "K8") (pinfunction "8_K8") (pintype "bidirectional"))
      (node (ref "T18") (pin "3") (pinfunction "C_3") (pintype "passive"))
    )
    (net (code "117") (name "/N1_9") (class "Default")
      (node (ref "N1") (pin "K9") (pinfunction "9_K9") (pintype "bidirectional"))
      (node (ref "T19") (pin "3") (pinfunction "C_3") (pintype "passive"))
    )
    (net (code "118") (name "/N1_DP") (class "Default")
      (node (ref "N1") (pin "KDP") (pinfunction "DP_KDP") (pintype "bidirectional"))
    )
    (net (code "119") (name "/N2_0") (class "Default")
      (node (ref "N2") (pin "K0") (pinfunction "0_K0") (pintype "bidirectional"))
      (node (ref "T20") (pin "3") (pinfunction "C_3") (pintype "passive"))
    )
    (net (code "120") (name "/N2_1") (class "Default")
      (node (ref "N2") (pin "K1") (pinfunction "1_K1") (pintype "bidirectional"))
      (node (ref "T21") (pin "3") (pinfunction "C_3") (pintype "passive"))
    )
    (net (code "121") (name "/N2_2") (class "Default")
      (node (ref "N2") (pin "K2") (pinfunction "2_K2") (pintype "bidirectional"))
      (node (ref "T22") (pin "3") (pinfunction "C_3") (pintype "passive"))
    )
    (net (code "122") (name "/N2_3") (class "Default")
      (node (ref "N2") (pin "K3") (pinfunction "3_K3") (pintype "bidirectional"))
      (node (ref "T23") (pin "3") (pinfunction "C_3") (pintype "passive"))
    )
    (net (code "123") (name "/N2_4") (class "Default")
      (node (ref "N2") (pin "K4") (pinfunction "4_K4") (pintype "bidirectional"))
      (node (ref "T24") (pin "3") (pinfunction "C_3") (pintype "passive"))
    )
    (net (code "124") (name "/N2_5") (class "Default")
      (node (ref "N2") (pin "K5") (pinfunction "5_K5") (pintype "bidirectional"))
      (node (ref "T25") (pin "3") (pinfunction "C_3") (pintype "passive"))
    )
    (net (code "125") (name "/N2_6") (class "Default")
      (node (ref "N2") (pin "K6") (pinfunction "6_K6") (pintype "bidirectional"))
      (node (ref "T26") (pin "3") (pinfunction "C_3") (pintype "passive"))
    )
    (net (code "126") (name "/N2_7") (class "Default")
      (node (ref "N2") (pin "K7") (pinfunction "7_K7") (pintype "bidirectional"))
      (node (ref "T27") (pin "3") (pinfunction "C_3") (pintype "passive"))
    )
    (net (code "127") (name "/N2_8") (class "Default")
      (node (ref "N2") (pin "K8") (pinfunction "8_K8") (pintype "bidirectional"))
      (node (ref "T28") (pin "3") (pinfunction "C_3") (pintype "passive"))
    )
    (net (code "128") (name "/N2_9") (class "Default")
      (node (ref "N2") (pin "K9") (pinfunction "9_K9") (pintype "bidirectional"))
      (node (ref "T29") (pin "3") (pinfunction "C_3") (pintype "passive"))
    )
    (net (code "129") (name "/N3_0") (class "Default")
      (node (ref "N3") (pin "K0") (pinfunction "0_K0") (pintype "bidirectional"))
      (node (ref "T30") (pin "3") (pinfunction "C_3") (pintype "passive"))
    )
    (net (code "130") (name "/N3_1") (class "Default")
      (node (ref "N3") (pin "K1") (pinfunction "1_K1") (pintype "bidirectional"))
      (node (ref "T31") (pin "3") (pinfunction "C_3") (pintype "passive"))
    )
    (net (code "131") (name "/N3_2") (class "Default")
      (node (ref "N3") (pin "K2") (pinfunction "2_K2") (pintype "bidirectional"))
      (node (ref "T32") (pin "3") (pinfunction "C_3") (pintype "passive"))
    )
    (net (code "132") (name "/N3_3") (class "Default")
      (node (ref "N3") (pin "K3") (pinfunction "3_K3") (pintype "bidirectional"))
      (node (ref "T33") (pin "3") (pinfunction "C_3") (pintype "passive"))
    )
    (net (code "133") (name "/N3_4") (class "Default")
      (node (ref "N3") (pin "K4") (pinfunction "4_K4") (pintype "bidirectional"))
      (node (ref "T34") (pin "3") (pinfunction "C_3") (pintype "passive"))
    )
    (net (code "134") (name "/N3_5") (class "Default")
      (node (ref "N3") (pin "K5") (pinfunction "5_K5") (pintype "bidirectional"))
      (node (ref "T35") (pin "3") (pinfunction "C_3") (pintype "passive"))
    )
    (net (code "135") (name "/N3_6") (class "Default")
      (node (ref "N3") (pin "K6") (pinfunction "6_K6") (pintype "bidirectional"))
      (node (ref "T36") (pin "3") (pinfunction "C_3") (pintype "passive"))
    )
    (net (code "136") (name "/N3_7") (class "Default")
      (node (ref "N3") (pin "K7") (pinfunction "7_K7") (pintype "bidirectional"))
      (node (ref "T37") (pin "3") (pinfunction "C_3") (pintype "passive"))
    )
    (net (code "137") (name "/N3_8") (class "Default")
      (node (ref "N3") (pin "K8") (pinfunction "8_K8") (pintype "bidirectional"))
      (node (ref "T38") (pin "3") (pinfunction "C_3") (pintype "passive"))
    )
    (net (code "138") (name "/N3_9") (class "Default")
      (node (ref "N3") (pin "K9") (pinfunction "9_K9") (pintype "bidirectional"))
      (node (ref "T39") (pin "3") (pinfunction "C_3") (pintype "passive"))
    )
    (net (code "139") (name "/RCK") (class "Default")
      (node (ref "IC1") (pin "12") (pinfunction "RCK_12") (pintype "input"))
      (node (ref "IC2") (pin "12") (pinfunction "RCK_12") (pintype "input"))
      (node (ref "IC3") (pin "12") (pinfunction "RCK_12") (pintype "input"))
      (node (ref "IC4") (pin "12") (pinfunction "RCK_12") (pintype "input"))
      (node (ref "IC5") (pin "12") (pinfunction "RCK_12") (pintype "input"))
      (node (ref "IC6") (pin "12") (pinfunction "RCK_12") (pintype "input"))
      (node (ref "JP1") (pin "9") (pinfunction "9_9") (pintype "passive"))
    )
    (net (code "140") (name "/SCK") (class "Default")
      (node (ref "IC1") (pin "11") (pinfunction "SCK_11") (pintype "input"))
      (node (ref "IC2") (pin "11") (pinfunction "SCK_11") (pintype "input"))
      (node (ref "IC3") (pin "11") (pinfunction "SCK_11") (pintype "input"))
      (node (ref "IC4") (pin "11") (pinfunction "SCK_11") (pintype "input"))
      (node (ref "IC5") (pin "11") (pinfunction "SCK_11") (pintype "input"))
      (node (ref "IC6") (pin "11") (pinfunction "SCK_11") (pintype "input"))
      (node (ref "JP1") (pin "10") (pinfunction "10_10") (pintype "passive"))
    )
    (net (code "141") (name "GND") (class "Default")
      (node (ref "C1") (pin "2") (pinfunction "2_2") (pintype "passive"))
      (node (ref "C2") (pin "2") (pinfunction "2_2") (pintype "passive"))
      (node (ref "C3") (pin "2") (pinfunction "2_2") (pintype "passive"))
      (node (ref "C4") (pin "2") (pinfunction "2_2") (pintype "passive"))
      (node (ref "C5") (pin "2") (pinfunction "2_2") (pintype "passive"))
      (node (ref "C6") (pin "2") (pinfunction "2_2") (pintype "passive"))
      (node (ref "IC1") (pin "8") (pinfunction "GND_8") (pintype "power_in"))
      (node (ref "IC2") (pin "8") (pinfunction "GND_8") (pintype "power_in"))
      (node (ref "IC3") (pin "8") (pinfunction "GND_8") (pintype "power_in"))
      (node (ref "IC4") (pin "8") (pinfunction "GND_8") (pintype "power_in"))
      (node (ref "IC5") (pin "8") (pinfunction "GND_8") (pintype "power_in"))
      (node (ref "IC6") (pin "8") (pinfunction "GND_8") (pintype "power_in"))
      (node (ref "JP1") (pin "2") (pinfunction "2_2") (pintype "passive"))
      (node (ref "JP1") (pin "3") (pinfunction "3_3") (pintype "passive"))
      (node (ref "JP1") (pin "4") (pinfunction "4_4") (pintype "passive"))
      (node (ref "JP1") (pin "5") (pinfunction "5_5") (pintype "passive"))
      (node (ref "R11") (pin "1") (pinfunction "1_1") (pintype "passive"))
      (node (ref "R21") (pin "1") (pinfunction "1_1") (pintype "passive"))
      (node (ref "R31") (pin "1") (pinfunction "1_1") (pintype "passive"))
      (node (ref "R41") (pin "1") (pinfunction "1_1") (pintype "passive"))
      (node (ref "T1") (pin "2") (pinfunction "E_2") (pintype "passive"))
      (node (ref "T10") (pin "2") (pinfunction "E_2") (pintype "passive"))
      (node (ref "T11") (pin "2") (pinfunction "E_2") (pintype "passive"))
      (node (ref "T12") (pin "2") (pinfunction "E_2") (pintype "passive"))
      (node (ref "T13") (pin "2") (pinfunction "E_2") (pintype "passive"))
      (node (ref "T14") (pin "2") (pinfunction "E_2") (pintype "passive"))
      (node (ref "T15") (pin "2") (pinfunction "E_2") (pintype "passive"))
      (node (ref "T16") (pin "2") (pinfunction "E_2") (pintype "passive"))
      (node (ref "T17") (pin "2") (pinfunction "E_2") (pintype "passive"))
      (node (ref "T18") (pin "2") (pinfunction "E_2") (pintype "passive"))
      (node (ref "T19") (pin "2") (pinfunction "E_2") (pintype "passive"))
      (node (ref "T2") (pin "2") (pinfunction "E_2") (pintype "passive"))
      (node (ref "T20") (pin "2") (pinfunction "E_2") (pintype "passive"))
      (node (ref "T21") (pin "2") (pinfunction "E_2") (pintype "passive"))
      (node (ref "T22") (pin "2") (pinfunction "E_2") (pintype "passive"))
      (node (ref "T23") (pin "2") (pinfunction "E_2") (pintype "passive"))
      (node (ref "T24") (pin "2") (pinfunction "E_2") (pintype "passive"))
      (node (ref "T25") (pin "2") (pinfunction "E_2") (pintype "passive"))
      (node (ref "T26") (pin "2") (pinfunction "E_2") (pintype "passive"))
      (node (ref "T27") (pin "2") (pinfunction "E_2") (pintype "passive"))
      (node (ref "T28") (pin "2") (pinfunction "E_2") (pintype "passive"))
      (node (ref "T29") (pin "2") (pinfunction "E_2") (pintype "passive"))
      (node (ref "T30") (pin "2") (pinfunction "E_2") (pintype "passive"))
      (node (ref "T31") (pin "2") (pinfunction "E_2") (pintype "passive"))
      (node (ref "T32") (pin "2") (pinfunction "E_2") (pintype "passive"))
      (node (ref "T33") (pin "2") (pinfunction "E_2") (pintype "passive"))
      (node (ref "T34") (pin "2") (pinfunction "E_2") (pintype "passive"))
      (node (ref "T35") (pin "2") (pinfunction "E_2") (pintype "passive"))
      (node (ref "T36") (pin "2") (pinfunction "E_2") (pintype "passive"))
      (node (ref "T37") (pin "2") (pinfunction "E_2") (pintype "passive"))
      (node (ref "T38") (pin "2") (pinfunction "E_2") (pintype "passive"))
      (node (ref "T39") (pin "2") (pinfunction "E_2") (pintype "passive"))
      (node (ref "T40") (pin "2") (pinfunction "E_2") (pintype "passive"))
      (node (ref "T41") (pin "2") (pinfunction "E_2") (pintype "passive"))
      (node (ref "T42") (pin "2") (pinfunction "E_2") (pintype "passive"))
      (node (ref "T43") (pin "2") (pinfunction "E_2") (pintype "passive"))
      (node (ref "T44") (pin "2") (pinfunction "E_2") (pintype "passive"))
      (node (ref "T45") (pin "2") (pinfunction "E_2") (pintype "passive"))
      (node (ref "T46") (pin "2") (pinfunction "E_2") (pintype "passive"))
      (node (ref "T47") (pin "2") (pinfunction "E_2") (pintype "passive"))
      (node (ref "T48") (pin "2") (pinfunction "E_2") (pintype "passive"))
      (node (ref "T49") (pin "2") (pinfunction "E_2") (pintype "passive"))
    )
    (net (code "142") (name "Net-(GL1-A)") (class "Default")
      (node (ref "GL1") (pin "1") (pinfunction "A_1") (pintype "passive"))
      (node (ref "R1") (pin "1") (pinfunction "1_1") (pintype "passive"))
    )
    (net (code "143") (name "Net-(GL1-A1)") (class "Default")
      (node (ref "GL1") (pin "2") (pinfunction "A1_2") (pintype "passive"))
      (node (ref "T1") (pin "3") (pinfunction "C_3") (pintype "passive"))
    )
    (net (code "144") (name "Net-(GL2-A)") (class "Default")
      (node (ref "GL2") (pin "1") (pinfunction "A_1") (pintype "passive"))
      (node (ref "R2") (pin "1") (pinfunction "1_1") (pintype "passive"))
    )
    (net (code "145") (name "Net-(GL2-A1)") (class "Default")
      (node (ref "GL2") (pin "2") (pinfunction "A1_2") (pintype "passive"))
      (node (ref "T2") (pin "3") (pinfunction "C_3") (pintype "passive"))
    )
    (net (code "146") (name "Net-(IC1A-QH*)") (class "Default")
      (node (ref "IC1") (pin "9") (pinfunction "QH*_9") (pintype "tri_state"))
      (node (ref "IC2") (pin "14") (pinfunction "SER_14") (pintype "input"))
    )
    (net (code "147") (name "Net-(IC2A-QH*)") (class "Default")
      (node (ref "IC2") (pin "9") (pinfunction "QH*_9") (pintype "tri_state"))
      (node (ref "IC3") (pin "14") (pinfunction "SER_14") (pintype "input"))
    )
    (net (code "148") (name "Net-(IC3A-QH*)") (class "Default")
      (node (ref "IC3") (pin "9") (pinfunction "QH*_9") (pintype "tri_state"))
      (node (ref "IC4") (pin "14") (pinfunction "SER_14") (pintype "input"))
    )
    (net (code "149") (name "Net-(IC4A-QH*)") (class "Default")
      (node (ref "IC4") (pin "9") (pinfunction "QH*_9") (pintype "tri_state"))
      (node (ref "IC5") (pin "14") (pinfunction "SER_14") (pintype "input"))
    )
    (net (code "150") (name "Net-(IC5A-QH*)") (class "Default")
      (node (ref "IC5") (pin "9") (pinfunction "QH*_9") (pintype "tri_state"))
      (node (ref "IC6") (pin "14") (pinfunction "SER_14") (pintype "input"))
    )
    (net (code "151") (name "Net-(N1-A-PadA1)") (class "Default")
      (node (ref "N1") (pin "A1") (pinfunction "A_A1") (pintype "bidirectional"))
      (node (ref "N1") (pin "A2") (pinfunction "A_A2") (pintype "bidirectional"))
      (node (ref "R10") (pin "1") (pinfunction "1_1") (pintype "passive"))
    )
    (net (code "152") (name "Net-(N1-PadPR)") (class "Default")
      (node (ref "N1") (pin "PR") (pinfunction "PR_PR") (pintype "bidirectional"))
      (node (ref "R11") (pin "2") (pinfunction "2_2") (pintype "passive"))
    )
    (net (code "153") (name "Net-(N2-A-PadA1)") (class "Default")
      (node (ref "N2") (pin "A1") (pinfunction "A_A1") (pintype "bidirectional"))
      (node (ref "N2") (pin "A2") (pinfunction "A_A2") (pintype "bidirectional"))
      (node (ref "R20") (pin "1") (pinfunction "1_1") (pintype "passive"))
    )
    (net (code "154") (name "Net-(N2-PadPR)") (class "Default")
      (node (ref "N2") (pin "PR") (pinfunction "PR_PR") (pintype "bidirectional"))
      (node (ref "R21") (pin "2") (pinfunction "2_2") (pintype "passive"))
    )
    (net (code "155") (name "Net-(N3-A-PadA1)") (class "Default")
      (node (ref "N3") (pin "A1") (pinfunction "A_A1") (pintype "bidirectional"))
      (node (ref "N3") (pin "A2") (pinfunction "A_A2") (pintype "bidirectional"))
      (node (ref "R30") (pin "1") (pinfunction "1_1") (pintype "passive"))
    )
    (net (code "156") (name "Net-(N3-PadPR)") (class "Default")
      (node (ref "N3") (pin "PR") (pinfunction "PR_PR") (pintype "bidirectional"))
      (node (ref "R31") (pin "2") (pinfunction "2_2") (pintype "passive"))
    )
    (net (code "157") (name "Net-(N4-A-PadA1)") (class "Default")
      (node (ref "N4") (pin "A1") (pinfunction "A_A1") (pintype "bidirectional"))
      (node (ref "N4") (pin "A2") (pinfunction "A_A2") (pintype "bidirectional"))
      (node (ref "R40") (pin "1") (pinfunction "1_1") (pintype "passive"))
    )
    (net (code "158") (name "Net-(N4-PadPR)") (class "Default")
      (node (ref "N4") (pin "PR") (pinfunction "PR_PR") (pintype "bidirectional"))
      (node (ref "R41") (pin "2") (pinfunction "2_2") (pintype "passive"))
    )
    (net (code "159") (name "VDD") (class "Default")
      (node (ref "JP1") (pin "1") (pinfunction "1_1") (pintype "passive"))
      (node (ref "R1") (pin "2") (pinfunction "2_2") (pintype "passive"))
      (node (ref "R10") (pin "2") (pinfunction "2_2") (pintype "passive"))
      (node (ref "R2") (pin "2") (pinfunction "2_2") (pintype "passive"))
      (node (ref "R20") (pin "2") (pinfunction "2_2") (pintype "passive"))
      (node (ref "R30") (pin "2") (pinfunction "2_2") (pintype "passive"))
      (node (ref "R40") (pin "2") (pinfunction "2_2") (pintype "passive"))
    )
    (net (code "160") (name "unconnected-(IC6A-QH*-Pad9)") (class "Default")
      (node (ref "IC6") (pin "9") (pinfunction "QH*_9") (pintype "tri_state"))
    )
    (net (code "161") (name "unconnected-(N2-DP-PadKDP)") (class "Default")
      (node (ref "N2") (pin "KDP") (pinfunction "DP_KDP") (pintype "bidirectional"))
    )
    (net (code "162") (name "unconnected-(N3-DP-PadKDP)") (class "Default")
      (node (ref "N3") (pin "KDP") (pinfunction "DP_KDP") (pintype "bidirectional"))
    )
    (net (code "163") (name "unconnected-(N4-DP-PadKDP)") (class "Default")
      (node (ref "N4") (pin "KDP") (pinfunction "DP_KDP") (pintype "bidirectional"))
    )
    (net (code "164") (name "unconnected-(RN31-Pad7)") (class "Default")
      (node (ref "RN31") (pin "7") (pinfunction "7_7") (pintype "passive"))
    )
    (net (code "165") (name "unconnected-(RN31-Pad8)") (class "Default")
      (node (ref "RN31") (pin "8") (pinfunction "8_8") (pintype "passive"))
    )
  )
)
